# untitled.net
KiCad netlist of a schematic drawn in EAGLE
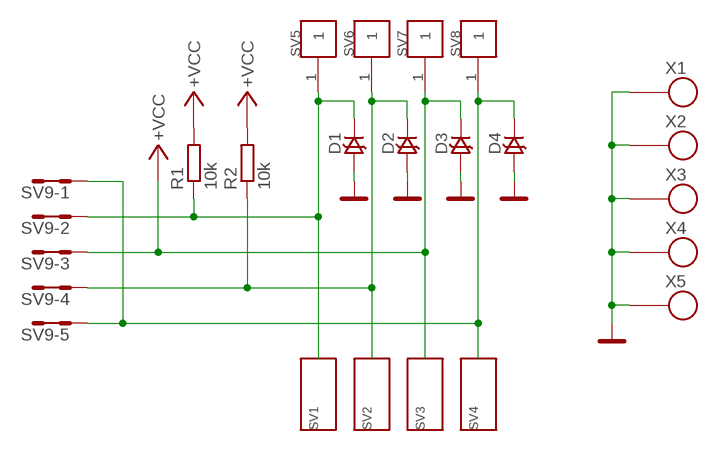
[diagram p0: schematic, sheet 1]

(export (version "E")
  (design (tool "Eeschema 10.0.6"))
  (components
    (comp (ref "D1")
      (value "D-TRANSIL-SMA")
      (footprint "eagle-import:SMA")
      (libsource (lib "eagle-import") (part "D-TRANSIL-SMA"))
    )
    (comp (ref "D2")
      (value "D-TRANSIL-SMA")
      (footprint "eagle-import:SMA")
      (libsource (lib "eagle-import") (part "D-TRANSIL-SMA"))
    )
    (comp (ref "D3")
      (value "D-TRANSIL-SMA")
      (footprint "eagle-import:SMA")
      (libsource (lib "eagle-import") (part "D-TRANSIL-SMA"))
    )
    (comp (ref "D4")
      (value "D-TRANSIL-SMA")
      (footprint "eagle-import:SMA")
      (libsource (lib "eagle-import") (part "D-TRANSIL-SMA"))
    )
    (comp (ref "R1")
      (value "10k")
      (footprint "eagle-import:0805")
      (libsource (lib "eagle-import") (part "R0805"))
    )
    (comp (ref "R2")
      (value "10k")
      (footprint "eagle-import:0805")
      (libsource (lib "eagle-import") (part "R0805"))
    )
    (comp (ref "SV1")
      (value "WAGO256")
      (footprint "eagle-import:WAGO256")
      (libsource (lib "eagle-import") (part "WAGO256"))
    )
    (comp (ref "SV2")
      (value "WAGO256")
      (footprint "eagle-import:WAGO256")
      (libsource (lib "eagle-import") (part "WAGO256"))
    )
    (comp (ref "SV3")
      (value "WAGO256")
      (footprint "eagle-import:WAGO256")
      (libsource (lib "eagle-import") (part "WAGO256"))
    )
    (comp (ref "SV4")
      (value "WAGO256")
      (footprint "eagle-import:WAGO256")
      (libsource (lib "eagle-import") (part "WAGO256"))
    )
    (comp (ref "SV5")
      (value "SMD:MA01-01")
      (footprint "eagle-import:SMD_MA01-1")
      (libsource (lib "eagle-import") (part "SMD{colon}MA01-01"))
    )
    (comp (ref "SV6")
      (value "SMD:MA01-01")
      (footprint "eagle-import:SMD_MA01-1")
      (libsource (lib "eagle-import") (part "SMD{colon}MA01-01"))
    )
    (comp (ref "SV7")
      (value "SMD:MA01-01")
      (footprint "eagle-import:SMD_MA01-1")
      (libsource (lib "eagle-import") (part "SMD{colon}MA01-01"))
    )
    (comp (ref "SV8")
      (value "SMD:MA01-01")
      (footprint "eagle-import:SMD_MA01-1")
      (libsource (lib "eagle-import") (part "SMD{colon}MA01-01"))
    )
    (comp (ref "SV9")
      (value "MA05-2")
      (footprint "eagle-import:MA05-2")
      (libsource (lib "eagle-import") (part "MA05-2"))
    )
    (comp (ref "X1")
      (value "SROUB3M")
      (footprint "eagle-import:SROUB3M")
      (libsource (lib "eagle-import") (part "SROUB3M"))
    )
    (comp (ref "X2")
      (value "SROUB3M")
      (footprint "eagle-import:SROUB3M")
      (libsource (lib "eagle-import") (part "SROUB3M"))
    )
    (comp (ref "X3")
      (value "SROUB3M")
      (footprint "eagle-import:SROUB3M")
      (libsource (lib "eagle-import") (part "SROUB3M"))
    )
    (comp (ref "X4")
      (value "SROUB3M")
      (footprint "eagle-import:SROUB3M")
      (libsource (lib "eagle-import") (part "SROUB3M"))
    )
    (comp (ref "X5")
      (value "SROUB3M")
      (footprint "eagle-import:SROUB3M")
      (libsource (lib "eagle-import") (part "SROUB3M"))
    )
  )
  (nets
    (net (code "1") (name "+VCC") (class "Default")
      (node (ref "D3") (pin "K") (pinfunction "K_K") (pintype "passive"))
      (node (ref "R1") (pin "2") (pinfunction "2_2") (pintype "passive"))
      (node (ref "R2") (pin "2") (pinfunction "2_2") (pintype "passive"))
      (node (ref "SV3") (pin "1") (pinfunction "P$1_1") (pintype "passive"))
      (node (ref "SV3") (pin "A1") (pinfunction "P$1_A1") (pintype "passive"))
      (node (ref "SV7") (pin "1") (pinfunction "1_1") (pintype "bidirectional"))
      (node (ref "SV9") (pin "5") (pinfunction "K_5") (pintype "passive"))
      (node (ref "SV9") (pin "6") (pinfunction "K_6") (pintype "passive"))
    )
    (net (code "2") (name "GND") (class "Default")
      (node (ref "D1") (pin "A") (pinfunction "A_A") (pintype "passive"))
      (node (ref "D2") (pin "A") (pinfunction "A_A") (pintype "passive"))
      (node (ref "D3") (pin "A") (pinfunction "A_A") (pintype "passive"))
      (node (ref "D4") (pin "A") (pinfunction "A_A") (pintype "passive"))
      (node (ref "X1") (pin "P$1") (pinfunction "P$1_P$1") (pintype "bidirectional"))
      (node (ref "X2") (pin "P$1") (pinfunction "P$1_P$1") (pintype "bidirectional"))
      (node (ref "X3") (pin "P$1") (pinfunction "P$1_P$1") (pintype "bidirectional"))
      (node (ref "X4") (pin "P$1") (pinfunction "P$1_P$1") (pintype "bidirectional"))
      (node (ref "X5") (pin "P$1") (pinfunction "P$1_P$1") (pintype "bidirectional"))
    )
    (net (code "3") (name "Net-(D1-PadK)") (class "Default")
      (node (ref "D1") (pin "K") (pinfunction "K_K") (pintype "passive"))
      (node (ref "R1") (pin "1") (pinfunction "1_1") (pintype "passive"))
      (node (ref "SV1") (pin "1") (pinfunction "P$1_1") (pintype "passive"))
      (node (ref "SV1") (pin "A1") (pinfunction "P$1_A1") (pintype "passive"))
      (node (ref "SV5") (pin "1") (pinfunction "1_1") (pintype "bidirectional"))
      (node (ref "SV9") (pin "3") (pinfunction "K_3") (pintype "passive"))
      (node (ref "SV9") (pin "4") (pinfunction "K_4") (pintype "passive"))
    )
    (net (code "4") (name "Net-(D2-PadK)") (class "Default")
      (node (ref "D2") (pin "K") (pinfunction "K_K") (pintype "passive"))
      (node (ref "R2") (pin "1") (pinfunction "1_1") (pintype "passive"))
      (node (ref "SV2") (pin "1") (pinfunction "P$1_1") (pintype "passive"))
      (node (ref "SV2") (pin "A1") (pinfunction "P$1_A1") (pintype "passive"))
      (node (ref "SV6") (pin "1") (pinfunction "1_1") (pintype "bidirectional"))
      (node (ref "SV9") (pin "7") (pinfunction "K_7") (pintype "passive"))
      (node (ref "SV9") (pin "8") (pinfunction "K_8") (pintype "passive"))
    )
    (net (code "5") (name "Net-(D4-PadK)") (class "Default")
      (node (ref "D4") (pin "K") (pinfunction "K_K") (pintype "passive"))
      (node (ref "SV4") (pin "1") (pinfunction "P$1_1") (pintype "passive"))
      (node (ref "SV4") (pin "A1") (pinfunction "P$1_A1") (pintype "passive"))
      (node (ref "SV8") (pin "1") (pinfunction "1_1") (pintype "bidirectional"))
      (node (ref "SV9") (pin "1") (pinfunction "K_1") (pintype "passive"))
      (node (ref "SV9") (pin "10") (pinfunction "K_10") (pintype "passive"))
      (node (ref "SV9") (pin "2") (pinfunction "K_2") (pintype "passive"))
      (node (ref "SV9") (pin "9") (pinfunction "K_9") (pintype "passive"))
    )
  )
)
